# ethernet.net
KiCad netlist of a schematic drawn in Altium Designer
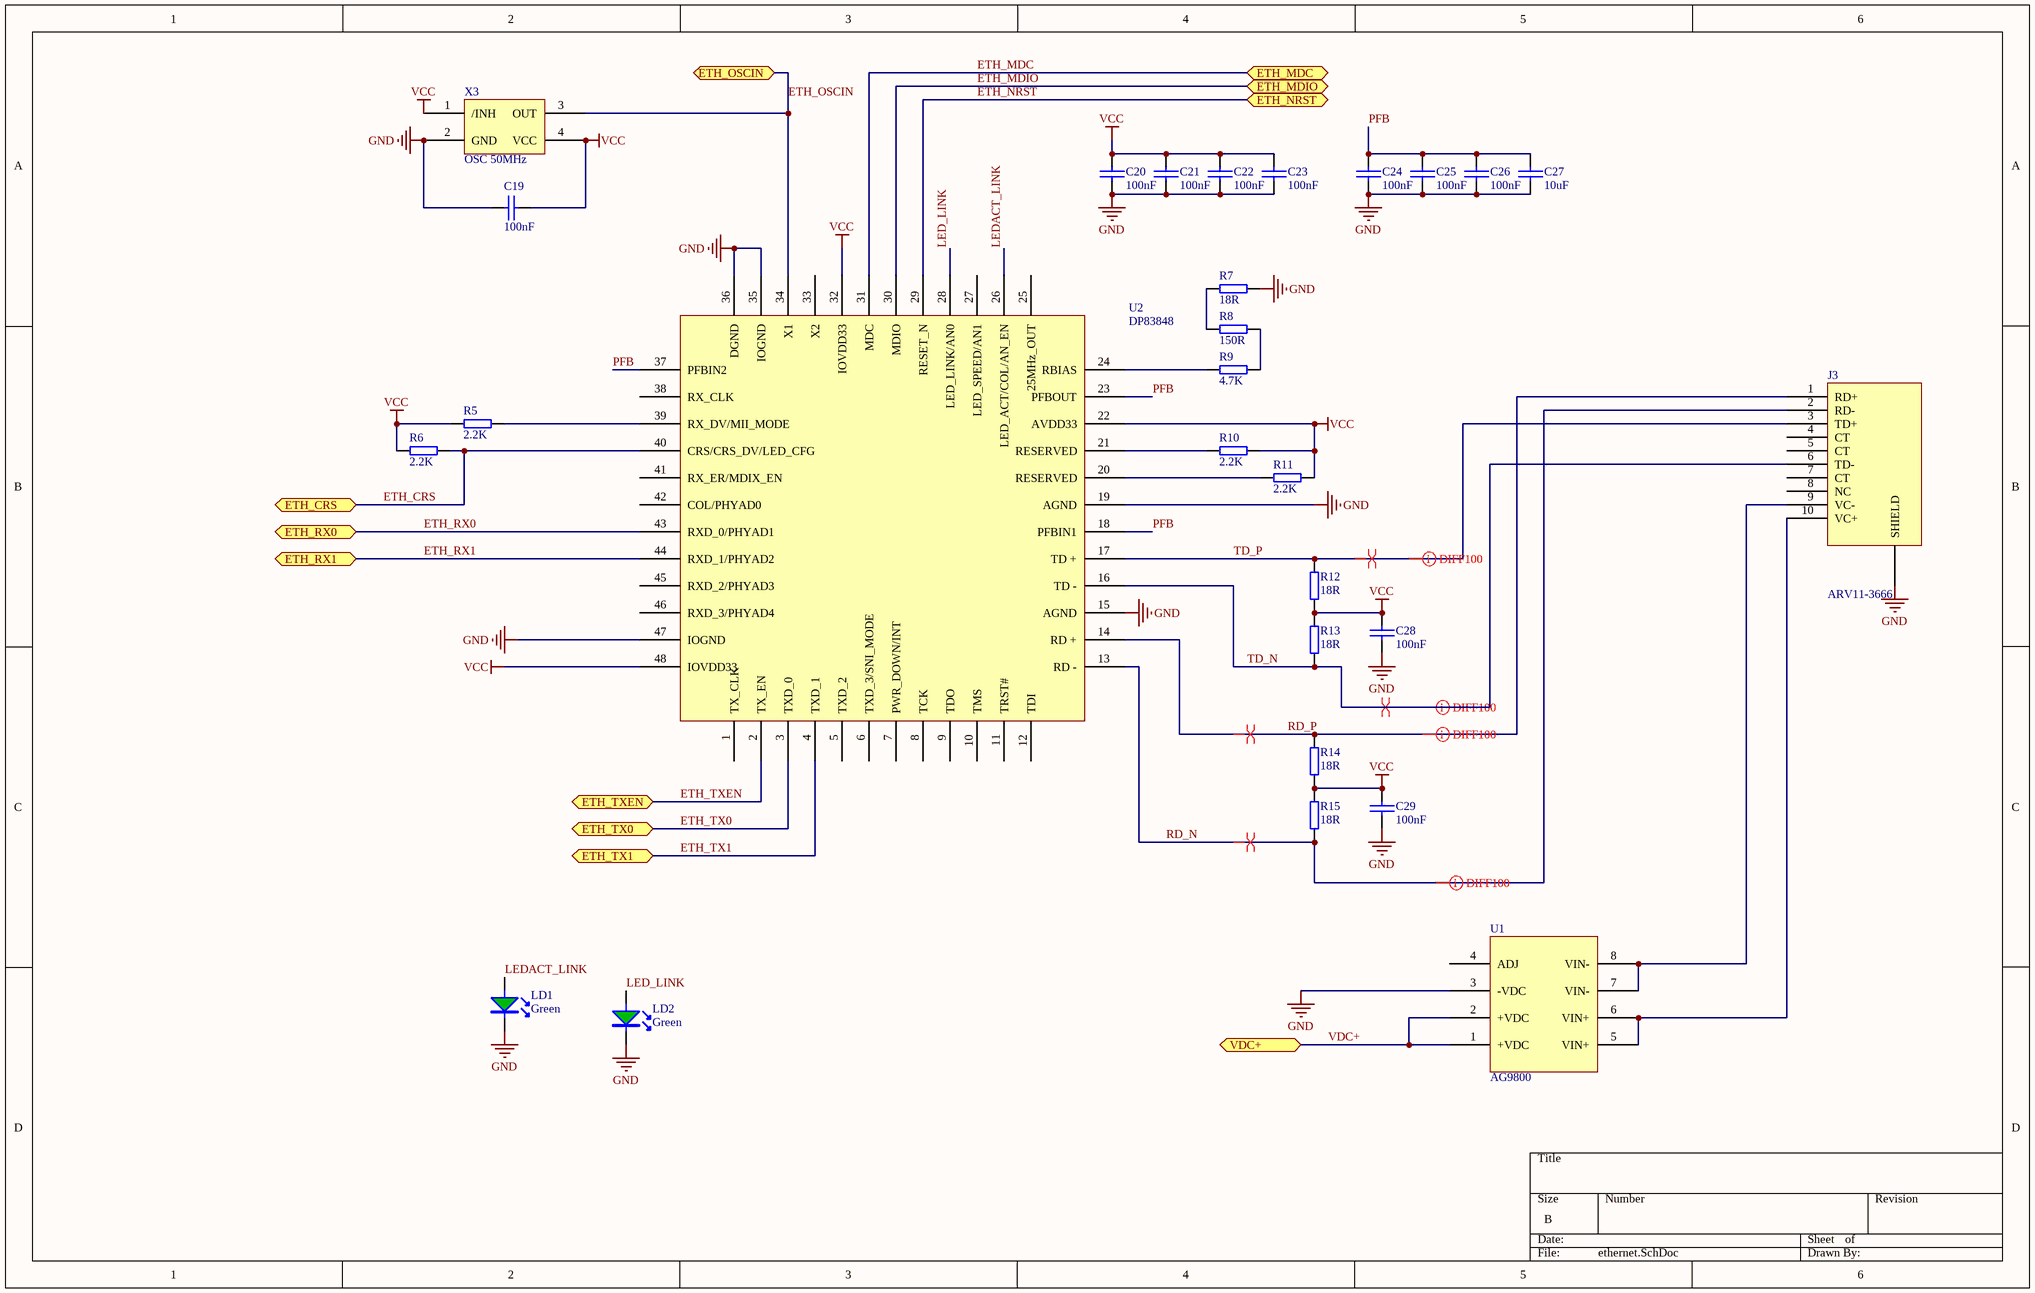
[diagram p0: ethernet.SchDoc]

(export (version "E")
  (design (tool "Eeschema 10.0.6"))
  (components
    (comp (ref "C19")
      (value "100nF")
      (footprint "0603-IPC")
      (description "0.01uF 50V")
      (libsource (lib "NAUTECH SCHEMATIC") (part "CAP 0603 XXX"))
    )
    (comp (ref "C20")
      (value "100nF")
      (footprint "0603-IPC")
      (description "0.01uF 50V")
      (libsource (lib "NAUTECH SCHEMATIC") (part "CAP 0603 XXX"))
    )
    (comp (ref "C21")
      (value "100nF")
      (footprint "0603-IPC")
      (description "0.01uF 50V")
      (libsource (lib "NAUTECH SCHEMATIC") (part "CAP 0603 XXX"))
    )
    (comp (ref "C22")
      (value "100nF")
      (footprint "0603-IPC")
      (description "0.01uF 50V")
      (libsource (lib "NAUTECH SCHEMATIC") (part "CAP 0603 XXX"))
    )
    (comp (ref "C23")
      (value "100nF")
      (footprint "0603-IPC")
      (description "0.01uF 50V")
      (libsource (lib "NAUTECH SCHEMATIC") (part "CAP 0603 XXX"))
    )
    (comp (ref "C24")
      (value "100nF")
      (footprint "0603-IPC")
      (description "0.01uF 50V")
      (libsource (lib "NAUTECH SCHEMATIC") (part "CAP 0603 XXX"))
    )
    (comp (ref "C25")
      (value "100nF")
      (footprint "0603-IPC")
      (description "0.01uF 50V")
      (libsource (lib "NAUTECH SCHEMATIC") (part "CAP 0603 XXX"))
    )
    (comp (ref "C26")
      (value "100nF")
      (footprint "0603-IPC")
      (description "0.01uF 50V")
      (libsource (lib "NAUTECH SCHEMATIC") (part "CAP 0603 XXX"))
    )
    (comp (ref "C27")
      (value "10uF")
      (footprint "0603-IPC")
      (description "0.01uF 50V")
      (libsource (lib "NAUTECH SCHEMATIC") (part "CAP 0603 XXX"))
    )
    (comp (ref "C28")
      (value "100nF")
      (footprint "0603-IPC")
      (description "0.01uF 50V")
      (libsource (lib "NAUTECH SCHEMATIC") (part "CAP 0603 XXX"))
    )
    (comp (ref "C29")
      (value "100nF")
      (footprint "0603-IPC")
      (description "0.01uF 50V")
      (libsource (lib "NAUTECH SCHEMATIC") (part "CAP 0603 XXX"))
    )
    (comp (ref "J3")
      (value "ARV11-3666")
      (footprint "ARV11-3666")
      (libsource (lib "corporatecam") (part "ARV11-3666"))
    )
    (comp (ref "LD1")
      (value "Green")
      (footprint "LED 0603-IPC")
      (description "LED Green 0603 Straight")
      (fields (field (name "MANUFACTURER") "Kingsbright") (field (name "POWER") "75mW"))
      (libsource (lib "corporatecam") (part "LED APT1608CGCK"))
    )
    (comp (ref "LD2")
      (value "Green")
      (footprint "LED 0603-IPC")
      (description "LED Green 0603 Straight")
      (fields (field (name "MANUFACTURER") "Kingsbright") (field (name "POWER") "75mW"))
      (libsource (lib "corporatecam") (part "LED APT1608CGCK"))
    )
    (comp (ref "R5")
      (value "2.2K")
      (footprint "0603-IPC")
      (description "RES0603")
      (libsource (lib "NAUTECH SCHEMATIC") (part "RES 0603 XXX"))
    )
    (comp (ref "R6")
      (value "2.2K")
      (footprint "0603-IPC")
      (description "RES0603")
      (libsource (lib "NAUTECH SCHEMATIC") (part "RES 0603 XXX"))
    )
    (comp (ref "R7")
      (value "18R")
      (footprint "0603-IPC")
      (description "RES0603")
      (libsource (lib "NAUTECH SCHEMATIC") (part "RES 0603 XXX"))
    )
    (comp (ref "R8")
      (value "150R")
      (footprint "0603-IPC")
      (description "RES0603")
      (libsource (lib "NAUTECH SCHEMATIC") (part "RES 0603 XXX"))
    )
    (comp (ref "R9")
      (value "4.7K")
      (footprint "0603-IPC")
      (description "RES0603")
      (libsource (lib "NAUTECH SCHEMATIC") (part "RES 0603 XXX"))
    )
    (comp (ref "R10")
      (value "2.2K")
      (footprint "0603-IPC")
      (description "RES0603")
      (libsource (lib "NAUTECH SCHEMATIC") (part "RES 0603 XXX"))
    )
    (comp (ref "R11")
      (value "2.2K")
      (footprint "0603-IPC")
      (description "RES0603")
      (libsource (lib "NAUTECH SCHEMATIC") (part "RES 0603 XXX"))
    )
    (comp (ref "R12")
      (value "18R")
      (footprint "0603-IPC")
      (description "RES0603")
      (libsource (lib "NAUTECH SCHEMATIC") (part "RES 0603 XXX"))
    )
    (comp (ref "R13")
      (value "18R")
      (footprint "0603-IPC")
      (description "RES0603")
      (libsource (lib "NAUTECH SCHEMATIC") (part "RES 0603 XXX"))
    )
    (comp (ref "R14")
      (value "18R")
      (footprint "0603-IPC")
      (description "RES0603")
      (libsource (lib "NAUTECH SCHEMATIC") (part "RES 0603 XXX"))
    )
    (comp (ref "R15")
      (value "18R")
      (footprint "0603-IPC")
      (description "RES0603")
      (libsource (lib "NAUTECH SCHEMATIC") (part "RES 0603 XXX"))
    )
    (comp (ref "U1") (value "AG9800") (footprint "AG9800") (libsource (lib "corporatecam") (part "AG9800")))
    (comp (ref "U2")
      (value "DP83848")
      (footprint "LQFP48_L")
      (libsource (lib "corporatecam") (part "DP83848"))
    )
    (comp (ref "X3")
      (value "OSC 50MHz")
      (footprint "Clock Osc")
      (description "KC3225A-C3")
      (libsource (lib "corporatecam") (part "KC3225A-C3"))
    )
  )
  (nets
    (net (code "1") (name "/ETH_CRS") (class "Default")
      (node (ref "R6") (pin "1") (pinfunction "1_1") (pintype "passive"))
      (node (ref "U2") (pin "40") (pinfunction "CRS/CRS_DV/LED_CFG_40") (pintype "passive"))
    )
    (net (code "2") (name "/ETH_MDC") (class "Default")
      (node (ref "U2") (pin "31") (pinfunction "MDC_31") (pintype "passive"))
    )
    (net (code "3") (name "/ETH_MDIO") (class "Default")
      (node (ref "U2") (pin "30") (pinfunction "MDIO_30") (pintype "passive"))
    )
    (net (code "4") (name "/ETH_NRST") (class "Default")
      (node (ref "U2") (pin "29") (pinfunction "RESET_N_29") (pintype "passive"))
    )
    (net (code "5") (name "/ETH_OSCIN") (class "Default")
      (node (ref "U2") (pin "34") (pinfunction "X1_34") (pintype "passive"))
      (node (ref "X3") (pin "3") (pinfunction "OUT_3") (pintype "passive"))
    )
    (net (code "6") (name "/ETH_RX0") (class "Default")
      (node (ref "U2") (pin "43") (pinfunction "RXD_0/PHYAD1_43") (pintype "passive"))
    )
    (net (code "7") (name "/ETH_RX1") (class "Default")
      (node (ref "U2") (pin "44") (pinfunction "RXD_1/PHYAD2_44") (pintype "passive"))
    )
    (net (code "8") (name "/ETH_TX0") (class "Default")
      (node (ref "U2") (pin "3") (pinfunction "TXD_0_3") (pintype "passive"))
    )
    (net (code "9") (name "/ETH_TX1") (class "Default")
      (node (ref "U2") (pin "4") (pinfunction "TXD_1_4") (pintype "passive"))
    )
    (net (code "10") (name "/ETH_TXEN") (class "Default")
      (node (ref "U2") (pin "2") (pinfunction "TX_EN_2") (pintype "passive"))
    )
    (net (code "11") (name "/LEDACT_LINK") (class "Default")
      (node (ref "LD1") (pin "A") (pinfunction "A_A") (pintype "passive"))
      (node (ref "U2") (pin "26") (pinfunction "LED_ACT/COL/AN_EN_26") (pintype "passive"))
    )
    (net (code "12") (name "/LED_LINK") (class "Default")
      (node (ref "LD2") (pin "A") (pinfunction "A_A") (pintype "passive"))
      (node (ref "U2") (pin "28") (pinfunction "LED_LINK/AN0_28") (pintype "passive"))
    )
    (net (code "13") (name "/PFB") (class "Default")
      (node (ref "C24") (pin "1") (pintype "passive"))
      (node (ref "C25") (pin "1") (pintype "passive"))
      (node (ref "C26") (pin "1") (pintype "passive"))
      (node (ref "C27") (pin "1") (pintype "passive"))
      (node (ref "U2") (pin "18") (pinfunction "PFBIN1_18") (pintype "passive"))
      (node (ref "U2") (pin "23") (pinfunction "PFBOUT_23") (pintype "passive"))
      (node (ref "U2") (pin "37") (pinfunction "PFBIN2_37") (pintype "passive"))
    )
    (net (code "14") (name "/RD_N") (class "Default")
      (node (ref "J3") (pin "2") (pinfunction "RD-_2") (pintype "passive"))
      (node (ref "R15") (pin "2") (pinfunction "2_2") (pintype "passive"))
      (node (ref "U2") (pin "13") (pinfunction "RD_-_13") (pintype "passive"))
    )
    (net (code "15") (name "/RD_P") (class "Default")
      (node (ref "J3") (pin "1") (pinfunction "RD+_1") (pintype "passive"))
      (node (ref "R14") (pin "1") (pinfunction "1_1") (pintype "passive"))
      (node (ref "U2") (pin "14") (pinfunction "RD_+_14") (pintype "passive"))
    )
    (net (code "16") (name "/TD_N") (class "Default")
      (node (ref "J3") (pin "6") (pinfunction "TD-_6") (pintype "passive"))
      (node (ref "R13") (pin "2") (pinfunction "2_2") (pintype "passive"))
      (node (ref "U2") (pin "16") (pinfunction "TD_-_16") (pintype "passive"))
    )
    (net (code "17") (name "/TD_P") (class "Default")
      (node (ref "J3") (pin "3") (pinfunction "TD+_3") (pintype "passive"))
      (node (ref "R12") (pin "1") (pinfunction "1_1") (pintype "passive"))
      (node (ref "U2") (pin "17") (pinfunction "TD_+_17") (pintype "passive"))
    )
    (net (code "18") (name "/VDC+") (class "Default")
      (node (ref "U1") (pin "1") (pinfunction "+VDC_1") (pintype "passive"))
      (node (ref "U1") (pin "2") (pinfunction "+VDC_2") (pintype "passive"))
    )
    (net (code "19") (name "GND") (class "Default")
      (node (ref "C19") (pin "2") (pintype "passive"))
      (node (ref "C20") (pin "2") (pintype "passive"))
      (node (ref "C21") (pin "2") (pintype "passive"))
      (node (ref "C22") (pin "2") (pintype "passive"))
      (node (ref "C23") (pin "2") (pintype "passive"))
      (node (ref "C24") (pin "2") (pintype "passive"))
      (node (ref "C25") (pin "2") (pintype "passive"))
      (node (ref "C26") (pin "2") (pintype "passive"))
      (node (ref "C27") (pin "2") (pintype "passive"))
      (node (ref "C28") (pin "2") (pintype "passive"))
      (node (ref "C29") (pin "2") (pintype "passive"))
      (node (ref "J3") (pin "11") (pinfunction "SHIELD_11") (pintype "passive"))
      (node (ref "LD1") (pin "K") (pinfunction "K_K") (pintype "passive"))
      (node (ref "LD2") (pin "K") (pinfunction "K_K") (pintype "passive"))
      (node (ref "R7") (pin "1") (pinfunction "1_1") (pintype "passive"))
      (node (ref "U1") (pin "3") (pinfunction "-VDC_3") (pintype "passive"))
      (node (ref "U2") (pin "15") (pinfunction "AGND_15") (pintype "passive"))
      (node (ref "U2") (pin "19") (pinfunction "AGND_19") (pintype "passive"))
      (node (ref "U2") (pin "35") (pinfunction "IOGND_35") (pintype "passive"))
      (node (ref "U2") (pin "36") (pinfunction "DGND_36") (pintype "passive"))
      (node (ref "U2") (pin "47") (pinfunction "IOGND_47") (pintype "passive"))
      (node (ref "X3") (pin "2") (pinfunction "GND_2") (pintype "passive"))
    )
    (net (code "20") (name "Net-(J3-VC+)") (class "Default")
      (node (ref "J3") (pin "10") (pinfunction "VC+_10") (pintype "passive"))
      (node (ref "U1") (pin "5") (pinfunction "VIN+_5") (pintype "passive"))
      (node (ref "U1") (pin "6") (pinfunction "VIN+_6") (pintype "passive"))
    )
    (net (code "21") (name "Net-(J3-VC-)") (class "Default")
      (node (ref "J3") (pin "9") (pinfunction "VC-_9") (pintype "passive"))
      (node (ref "U1") (pin "7") (pinfunction "VIN-_7") (pintype "passive"))
      (node (ref "U1") (pin "8") (pinfunction "VIN-_8") (pintype "passive"))
    )
    (net (code "22") (name "Net-(R7-Pad2)") (class "Default")
      (node (ref "R7") (pin "2") (pinfunction "2_2") (pintype "passive"))
      (node (ref "R8") (pin "2") (pinfunction "2_2") (pintype "passive"))
    )
    (net (code "23") (name "Net-(R8-Pad1)") (class "Default")
      (node (ref "R8") (pin "1") (pinfunction "1_1") (pintype "passive"))
      (node (ref "R9") (pin "1") (pinfunction "1_1") (pintype "passive"))
    )
    (net (code "24") (name "Net-(R10-Pad2)") (class "Default")
      (node (ref "R10") (pin "2") (pinfunction "2_2") (pintype "passive"))
      (node (ref "U2") (pin "21") (pinfunction "RESERVED_21") (pintype "passive"))
    )
    (net (code "25") (name "Net-(R11-Pad2)") (class "Default")
      (node (ref "R11") (pin "2") (pinfunction "2_2") (pintype "passive"))
      (node (ref "U2") (pin "20") (pinfunction "RESERVED_20") (pintype "passive"))
    )
    (net (code "26") (name "Net-(U2-RBIAS)") (class "Default")
      (node (ref "R9") (pin "2") (pinfunction "2_2") (pintype "passive"))
      (node (ref "U2") (pin "24") (pinfunction "RBIAS_24") (pintype "passive"))
    )
    (net (code "27") (name "Net-(U2-RX_DV{slash}MII_MODE)") (class "Default")
      (node (ref "R5") (pin "1") (pinfunction "1_1") (pintype "passive"))
      (node (ref "U2") (pin "39") (pinfunction "RX_DV/MII_MODE_39") (pintype "passive"))
    )
    (net (code "28") (name "VCC") (class "Default")
      (node (ref "C19") (pin "1") (pintype "passive"))
      (node (ref "C20") (pin "1") (pintype "passive"))
      (node (ref "C21") (pin "1") (pintype "passive"))
      (node (ref "C22") (pin "1") (pintype "passive"))
      (node (ref "C23") (pin "1") (pintype "passive"))
      (node (ref "C28") (pin "1") (pintype "passive"))
      (node (ref "C29") (pin "1") (pintype "passive"))
      (node (ref "R10") (pin "1") (pinfunction "1_1") (pintype "passive"))
      (node (ref "R11") (pin "1") (pinfunction "1_1") (pintype "passive"))
      (node (ref "R12") (pin "2") (pinfunction "2_2") (pintype "passive"))
      (node (ref "R13") (pin "1") (pinfunction "1_1") (pintype "passive"))
      (node (ref "R14") (pin "2") (pinfunction "2_2") (pintype "passive"))
      (node (ref "R15") (pin "1") (pinfunction "1_1") (pintype "passive"))
      (node (ref "R5") (pin "2") (pinfunction "2_2") (pintype "passive"))
      (node (ref "R6") (pin "2") (pinfunction "2_2") (pintype "passive"))
      (node (ref "U2") (pin "22") (pinfunction "AVDD33_22") (pintype "passive"))
      (node (ref "U2") (pin "32") (pinfunction "IOVDD33_32") (pintype "passive"))
      (node (ref "U2") (pin "48") (pinfunction "IOVDD33_48") (pintype "passive"))
      (node (ref "X3") (pin "1") (pinfunction "/INH_1") (pintype "passive"))
      (node (ref "X3") (pin "4") (pinfunction "VCC_4") (pintype "passive"))
    )
    (net (code "29") (name "unconnected-(J3-CT-Pad4)") (class "Default")
      (node (ref "J3") (pin "4") (pinfunction "CT_4") (pintype "passive"))
    )
    (net (code "30") (name "unconnected-(J3-CT-Pad5)") (class "Default")
      (node (ref "J3") (pin "5") (pinfunction "CT_5") (pintype "passive"))
    )
    (net (code "31") (name "unconnected-(J3-CT-Pad7)") (class "Default")
      (node (ref "J3") (pin "7") (pinfunction "CT_7") (pintype "passive"))
    )
    (net (code "32") (name "unconnected-(J3-NC-Pad8)") (class "Default")
      (node (ref "J3") (pin "8") (pinfunction "NC_8") (pintype "passive"))
    )
    (net (code "33") (name "unconnected-(U1-ADJ-Pad4)") (class "Default")
      (node (ref "U1") (pin "4") (pinfunction "ADJ_4") (pintype "passive"))
    )
    (net (code "34") (name "unconnected-(U2-25MHz_OUT-Pad25)") (class "Default")
      (node (ref "U2") (pin "25") (pinfunction "25MHz_OUT_25") (pintype "passive"))
    )
    (net (code "35") (name "unconnected-(U2-COL{slash}PHYAD0-Pad42)") (class "Default")
      (node (ref "U2") (pin "42") (pinfunction "COL/PHYAD0_42") (pintype "passive"))
    )
    (net (code "36") (name "unconnected-(U2-LED_SPEED{slash}AN1-Pad27)") (class "Default")
      (node (ref "U2") (pin "27") (pinfunction "LED_SPEED/AN1_27") (pintype "passive"))
    )
    (net (code "37") (name "unconnected-(U2-PWR_DOWN{slash}INT-Pad7)") (class "Default")
      (node (ref "U2") (pin "7") (pinfunction "PWR_DOWN/INT_7") (pintype "passive"))
    )
    (net (code "38") (name "unconnected-(U2-RXD_2{slash}PHYAD3-Pad45)") (class "Default")
      (node (ref "U2") (pin "45") (pinfunction "RXD_2/PHYAD3_45") (pintype "passive"))
    )
    (net (code "39") (name "unconnected-(U2-RXD_3{slash}PHYAD4-Pad46)") (class "Default")
      (node (ref "U2") (pin "46") (pinfunction "RXD_3/PHYAD4_46") (pintype "passive"))
    )
    (net (code "40") (name "unconnected-(U2-RX_CLK-Pad38)") (class "Default")
      (node (ref "U2") (pin "38") (pinfunction "RX_CLK_38") (pintype "passive"))
    )
    (net (code "41") (name "unconnected-(U2-RX_ER{slash}MDIX_EN-Pad41)") (class "Default")
      (node (ref "U2") (pin "41") (pinfunction "RX_ER/MDIX_EN_41") (pintype "passive"))
    )
    (net (code "42") (name "unconnected-(U2-TCK-Pad8)") (class "Default")
      (node (ref "U2") (pin "8") (pinfunction "TCK_8") (pintype "passive"))
    )
    (net (code "43") (name "unconnected-(U2-TDI-Pad12)") (class "Default")
      (node (ref "U2") (pin "12") (pinfunction "TDI_12") (pintype "passive"))
    )
    (net (code "44") (name "unconnected-(U2-TDO-Pad9)") (class "Default")
      (node (ref "U2") (pin "9") (pinfunction "TDO_9") (pintype "passive"))
    )
    (net (code "45") (name "unconnected-(U2-TMS-Pad10)") (class "Default")
      (node (ref "U2") (pin "10") (pinfunction "TMS_10") (pintype "passive"))
    )
    (net (code "46") (name "unconnected-(U2-TRST#-Pad11)") (class "Default")
      (node (ref "U2") (pin "11") (pinfunction "TRST#_11") (pintype "passive"))
    )
    (net (code "47") (name "unconnected-(U2-TXD_2-Pad5)") (class "Default")
      (node (ref "U2") (pin "5") (pinfunction "TXD_2_5") (pintype "passive"))
    )
    (net (code "48") (name "unconnected-(U2-TXD_3{slash}SNI_MODE-Pad6)") (class "Default")
      (node (ref "U2") (pin "6") (pinfunction "TXD_3/SNI_MODE_6") (pintype "passive"))
    )
    (net (code "49") (name "unconnected-(U2-TX_CLK-Pad1)") (class "Default")
      (node (ref "U2") (pin "1") (pinfunction "TX_CLK_1") (pintype "passive"))
    )
    (net (code "50") (name "unconnected-(U2-X2-Pad33)") (class "Default")
      (node (ref "U2") (pin "33") (pinfunction "X2_33") (pintype "passive"))
    )
  )
)
